# X12_Power_Distribuition.net
KiCad netlist of a schematic drawn in EAGLE
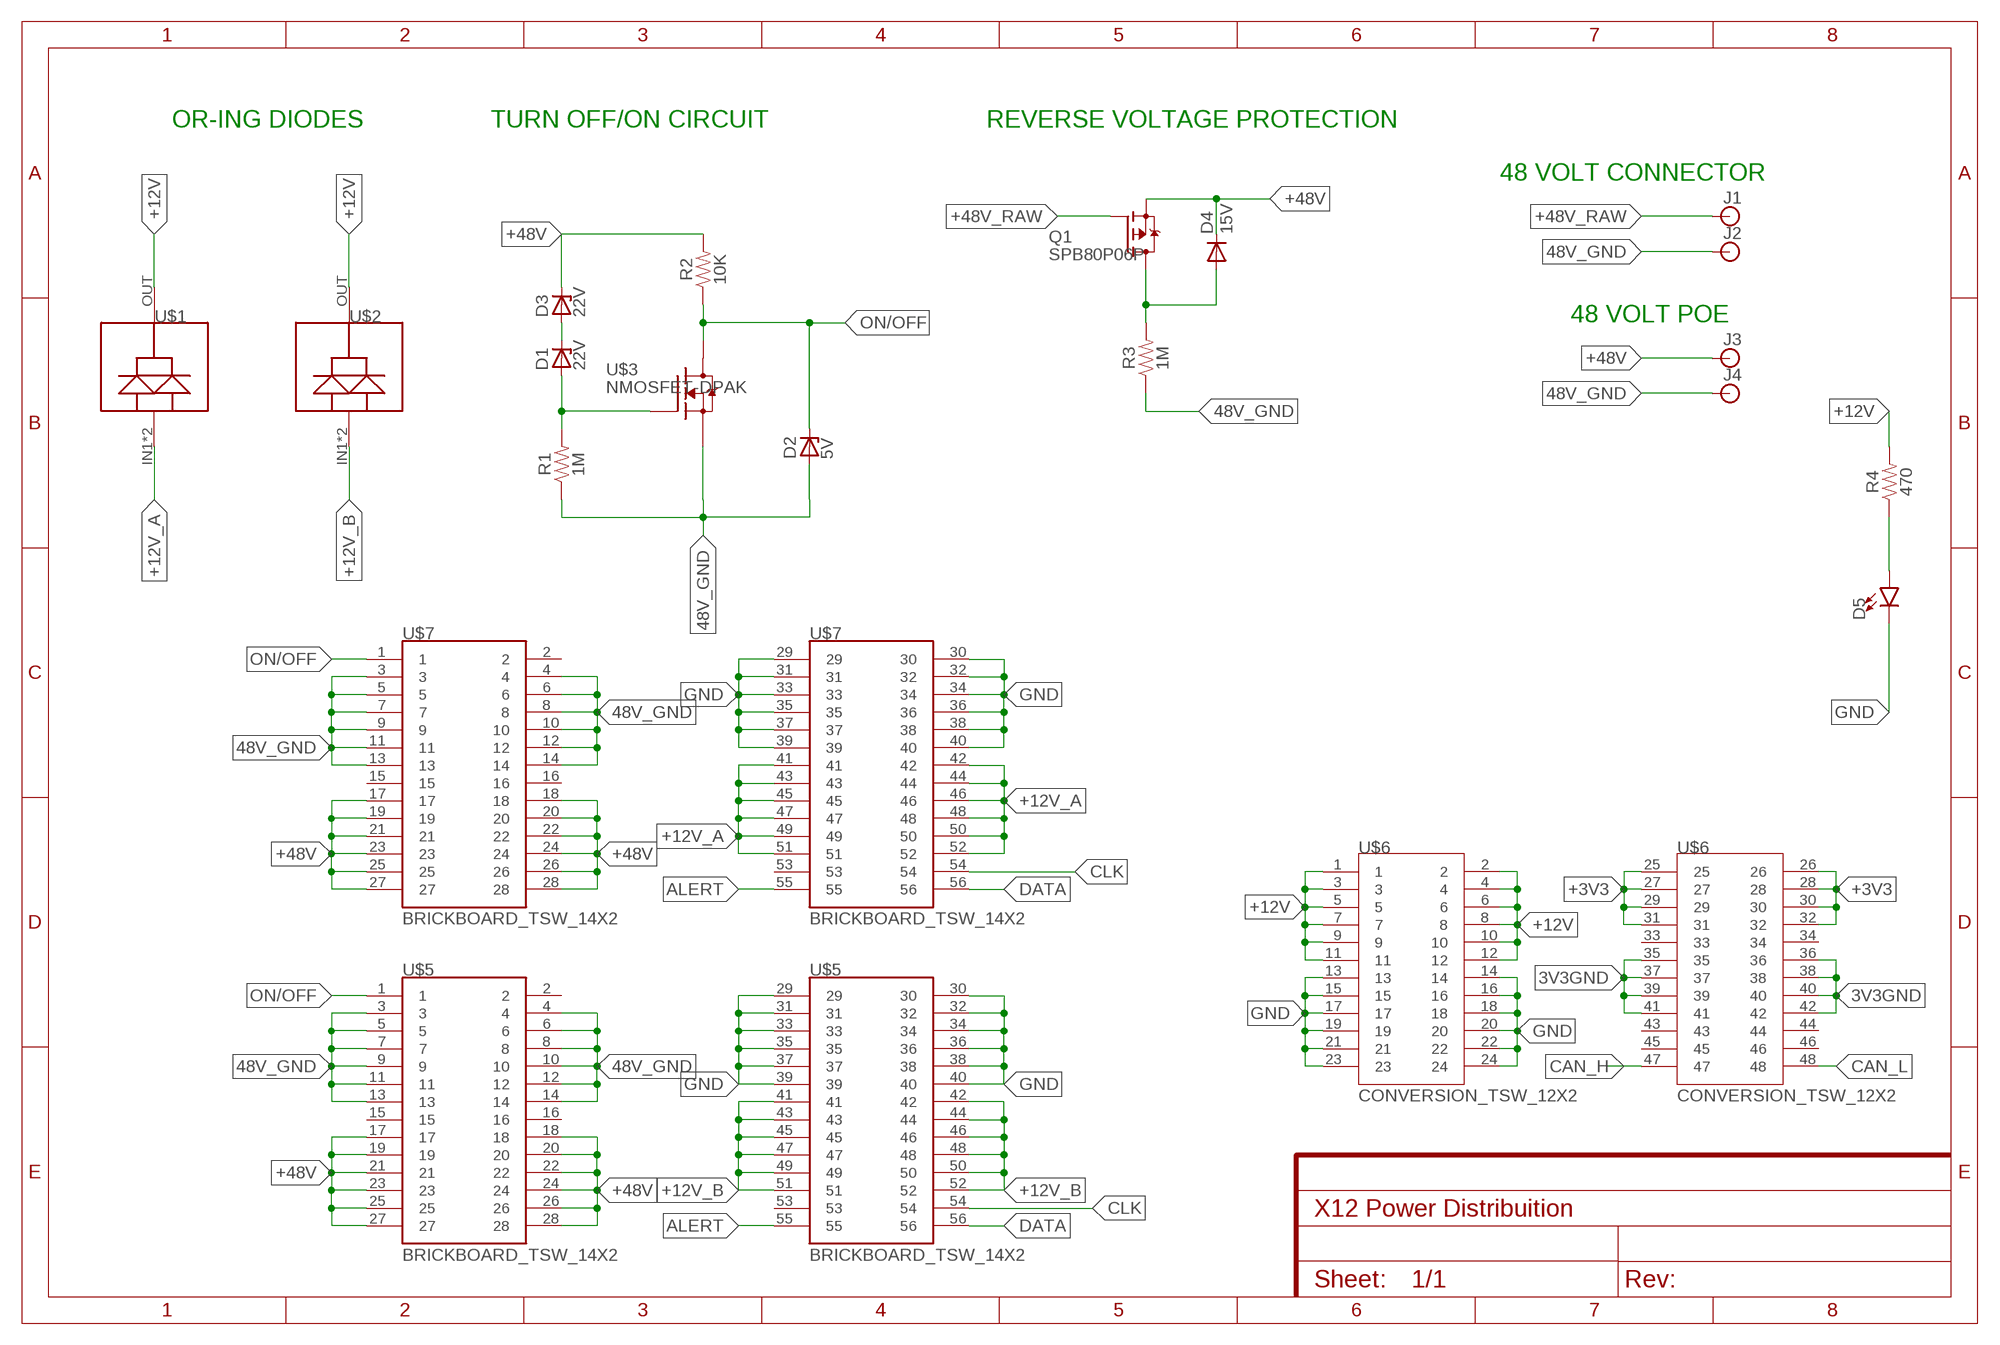
[diagram p0: schematic, sheet 1, part 1 of 2]
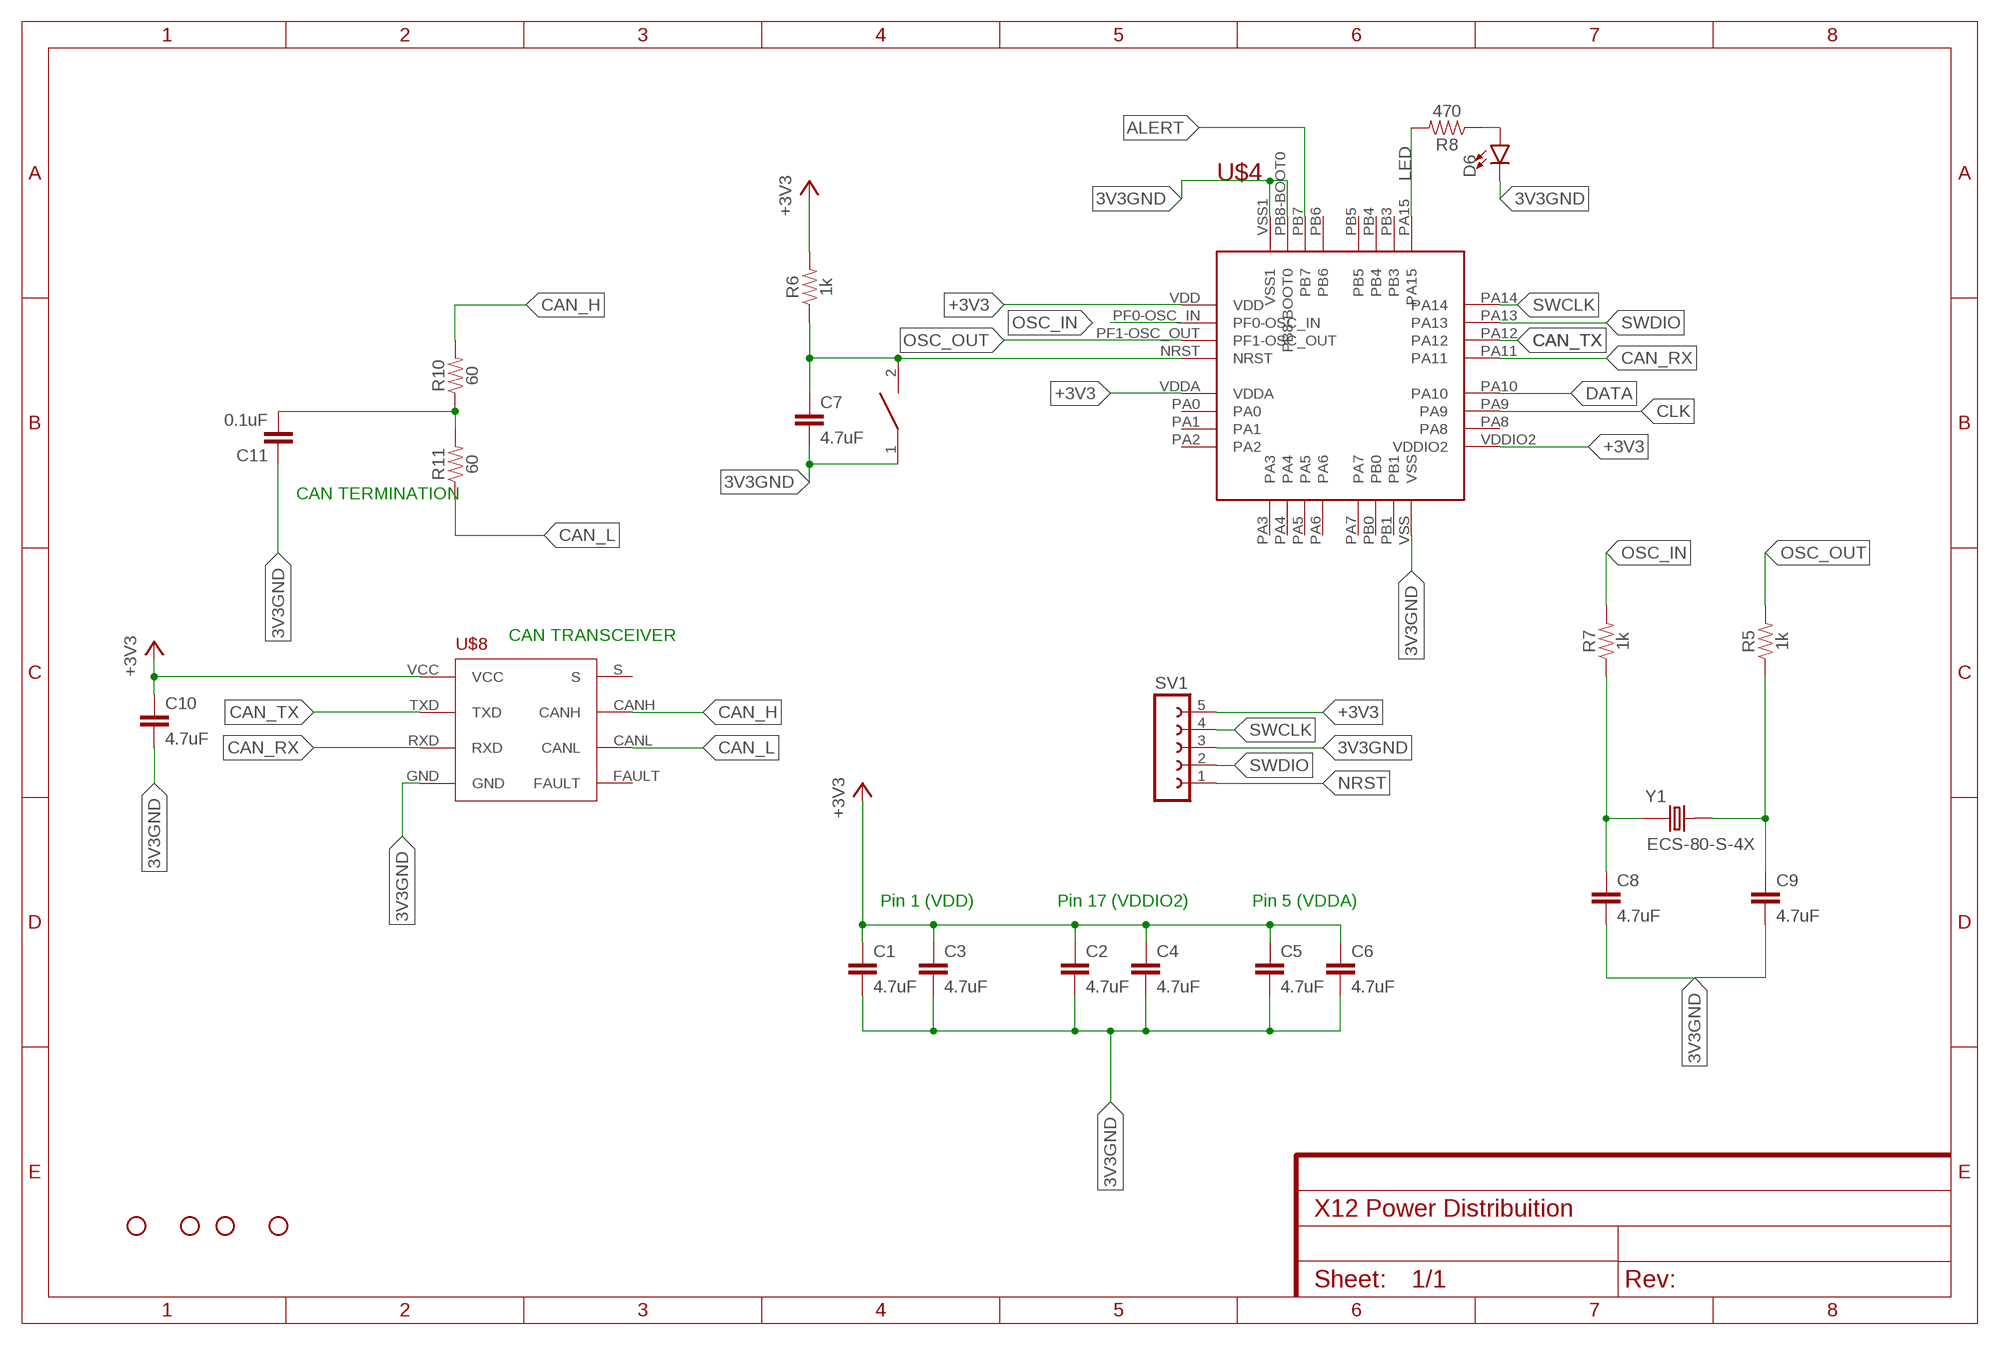
[diagram p1: schematic, sheet 1, part 2 of 2]

(export (version "E")
  (design (tool "Eeschema 10.0.6"))
  (components
    (comp (ref "C1")
      (value "4.7uF")
      (footprint "eagle-import:0603")
      (libsource (lib "eagle-import") (part "4.7UF0603"))
    )
    (comp (ref "C2")
      (value "4.7uF")
      (footprint "eagle-import:0603")
      (libsource (lib "eagle-import") (part "4.7UF0603"))
    )
    (comp (ref "C3")
      (value "4.7uF")
      (footprint "eagle-import:0603")
      (libsource (lib "eagle-import") (part "4.7UF0603"))
    )
    (comp (ref "C4")
      (value "4.7uF")
      (footprint "eagle-import:0603")
      (libsource (lib "eagle-import") (part "4.7UF0603"))
    )
    (comp (ref "C5")
      (value "4.7uF")
      (footprint "eagle-import:0603")
      (libsource (lib "eagle-import") (part "4.7UF0603"))
    )
    (comp (ref "C6")
      (value "4.7uF")
      (footprint "eagle-import:0603")
      (libsource (lib "eagle-import") (part "4.7UF0603"))
    )
    (comp (ref "C7")
      (value "4.7uF")
      (footprint "eagle-import:0603")
      (libsource (lib "eagle-import") (part "4.7UF0603"))
    )
    (comp (ref "C8")
      (value "4.7uF")
      (footprint "eagle-import:0603")
      (libsource (lib "eagle-import") (part "4.7UF0603"))
    )
    (comp (ref "C9")
      (value "4.7uF")
      (footprint "eagle-import:0603")
      (libsource (lib "eagle-import") (part "4.7UF0603"))
    )
    (comp (ref "C10")
      (value "4.7uF")
      (footprint "eagle-import:0603")
      (libsource (lib "eagle-import") (part "4.7UF0603"))
    )
    (comp (ref "C11")
      (value "0.1uF")
      (footprint "eagle-import:0603")
      (libsource (lib "eagle-import") (part "0.1UF-0603-25V-(+80/-20%)"))
    )
    (comp (ref "D1")
      (value "22V")
      (footprint "eagle-import:SOT23")
      (libsource (lib "eagle-import") (part "ZENER-DIODESOT23"))
    )
    (comp (ref "D2")
      (value "5V")
      (footprint "eagle-import:SOT23")
      (libsource (lib "eagle-import") (part "ZENER-DIODESOT23"))
    )
    (comp (ref "D3")
      (value "22V")
      (footprint "eagle-import:SOT23")
      (libsource (lib "eagle-import") (part "ZENER-DIODESOT23"))
    )
    (comp (ref "D4")
      (value "15V")
      (footprint "eagle-import:SOD123")
      (libsource (lib "eagle-import") (part "DIODE-SOD123"))
    )
    (comp (ref "D5")
      (value "LED0603")
      (footprint "eagle-import:LED-0603")
      (libsource (lib "eagle-import") (part "LED0603"))
    )
    (comp (ref "D6")
      (value "LED0603")
      (footprint "eagle-import:LED-0603")
      (libsource (lib "eagle-import") (part "LED0603"))
    )
    (comp (ref "H1")
      (value "STAND-OFF")
      (footprint "eagle-import:STAND-OFF")
      (libsource (lib "eagle-import") (part "STAND-OFF"))
    )
    (comp (ref "H2")
      (value "STAND-OFF")
      (footprint "eagle-import:STAND-OFF")
      (libsource (lib "eagle-import") (part "STAND-OFF"))
    )
    (comp (ref "H3")
      (value "STAND-OFF")
      (footprint "eagle-import:STAND-OFF")
      (libsource (lib "eagle-import") (part "STAND-OFF"))
    )
    (comp (ref "H4")
      (value "STAND-OFF")
      (footprint "eagle-import:STAND-OFF")
      (libsource (lib "eagle-import") (part "STAND-OFF"))
    )
    (comp (ref "J1")
      (value "BANANA_CONN")
      (footprint "eagle-import:BANANA_CONN")
      (libsource (lib "eagle-import") (part "BANANA_CONN"))
    )
    (comp (ref "J2")
      (value "BANANA_CONN")
      (footprint "eagle-import:BANANA_CONN")
      (libsource (lib "eagle-import") (part "BANANA_CONN"))
    )
    (comp (ref "J3")
      (value "BANANA_CONN")
      (footprint "eagle-import:BANANA_CONN")
      (libsource (lib "eagle-import") (part "BANANA_CONN"))
    )
    (comp (ref "J4")
      (value "BANANA_CONN")
      (footprint "eagle-import:BANANA_CONN")
      (libsource (lib "eagle-import") (part "BANANA_CONN"))
    )
    (comp (ref "Q1")
      (value "SPB80P06P")
      (footprint "eagle-import:TO263")
      (libsource (lib "eagle-import") (part "SPB80P06P"))
    )
    (comp (ref "R1")
      (value "1M")
      (footprint "eagle-import:0603")
      (fields (field (name "SPICEPREFIX") "R"))
      (libsource (lib "eagle-import") (part "RESISTOR0603"))
    )
    (comp (ref "R2")
      (value "10K")
      (footprint "eagle-import:0603")
      (fields (field (name "SPICEPREFIX") "R"))
      (libsource (lib "eagle-import") (part "RESISTOR0603"))
    )
    (comp (ref "R3")
      (value "1M")
      (footprint "eagle-import:0603")
      (fields (field (name "SPICEPREFIX") "R"))
      (libsource (lib "eagle-import") (part "RESISTOR0603"))
    )
    (comp (ref "R4")
      (value "470")
      (footprint "eagle-import:0603")
      (libsource (lib "eagle-import") (part "RESISTOR0603"))
    )
    (comp (ref "R5")
      (value "1k")
      (footprint "eagle-import:0603")
      (libsource (lib "eagle-import") (part "1KOHM-0603-1/10W-1%"))
    )
    (comp (ref "R6")
      (value "1k")
      (footprint "eagle-import:0603")
      (libsource (lib "eagle-import") (part "1KOHM-0603-1/10W-1%"))
    )
    (comp (ref "R7")
      (value "1k")
      (footprint "eagle-import:0603")
      (libsource (lib "eagle-import") (part "1KOHM-0603-1/10W-1%"))
    )
    (comp (ref "R8")
      (value "470")
      (footprint "eagle-import:0603")
      (libsource (lib "eagle-import") (part "RESISTOR0603"))
    )
    (comp (ref "R10")
      (value "60")
      (footprint "eagle-import:0603")
      (libsource (lib "eagle-import") (part "1KOHM-0603-1/10W-1%"))
    )
    (comp (ref "R11")
      (value "60")
      (footprint "eagle-import:0603")
      (libsource (lib "eagle-import") (part "1KOHM-0603-1/10W-1%"))
    )
    (comp (ref "RESET")
      (value "SWITCH")
      (footprint "eagle-import:SW_2512")
      (libsource (lib "eagle-import") (part "SWITCH"))
    )
    (comp (ref "SV1")
      (value "FE05-1")
      (footprint "eagle-import:FE05-1")
      (libsource (lib "eagle-import") (part "FE05-1"))
    )
    (comp (ref "U$1")
      (value "DIODE")
      (footprint "eagle-import:DIODE")
      (libsource (lib "eagle-import") (part "DIODE"))
    )
    (comp (ref "U$2")
      (value "DIODE")
      (footprint "eagle-import:DIODE")
      (libsource (lib "eagle-import") (part "DIODE"))
    )
    (comp (ref "U$3")
      (value "NMOSFET-DPAK")
      (footprint "eagle-import:DPAK")
      (libsource (lib "eagle-import") (part "NMOSFET-DPAK"))
    )
    (comp (ref "U$4")
      (value "STM32F042K6T6")
      (footprint "eagle-import:STM32F042K6T6")
      (libsource (lib "eagle-import") (part "STM32F042K6T6"))
    )
    (comp (ref "U$5")
      (value "BRICKBOARD_TSW_14X2")
      (footprint "eagle-import:BRICKBOARD_TSW_14X2")
      (libsource (lib "eagle-import") (part "BRICKBOARD_TSW_14X2"))
    )
    (comp (ref "U$6")
      (value "CONVERSION_TSW_12X2")
      (footprint "eagle-import:CONVERSION_TSW_12X2")
      (libsource (lib "eagle-import") (part "CONVERSION_TSW_12X2"))
    )
    (comp (ref "U$7")
      (value "BRICKBOARD_TSW_14X2")
      (footprint "eagle-import:BRICKBOARD_TSW_14X2")
      (libsource (lib "eagle-import") (part "BRICKBOARD_TSW_14X2"))
    )
    (comp (ref "U$8")
      (value "TCAN337D")
      (footprint "eagle-import:TCAN337D")
      (libsource (lib "eagle-import") (part "TCAN337D"))
    )
    (comp (ref "Y1")
      (value "ECS-80-S-4X")
      (footprint "eagle-import:XTAL_ECS-80-S-4X")
      (fields (field (name "DIGI-KEY_PART_NUMBER") "X1057-ND") (field (name "MF") "ECS International"))
      (libsource (lib "eagle-import") (part "ECS-80-S-4X"))
    )
  )
  (nets
    (net (code "1") (name "+3V3") (class "Default")
      (node (ref "C1") (pin "1") (pinfunction "1_1") (pintype "passive"))
      (node (ref "C10") (pin "1") (pinfunction "1_1") (pintype "passive"))
      (node (ref "C2") (pin "1") (pinfunction "1_1") (pintype "passive"))
      (node (ref "C3") (pin "1") (pinfunction "1_1") (pintype "passive"))
      (node (ref "C4") (pin "1") (pinfunction "1_1") (pintype "passive"))
      (node (ref "C5") (pin "1") (pinfunction "1_1") (pintype "passive"))
      (node (ref "C6") (pin "1") (pinfunction "1_1") (pintype "passive"))
      (node (ref "R6") (pin "2") (pinfunction "2_2") (pintype "passive"))
      (node (ref "SV1") (pin "5") (pinfunction "5_5") (pintype "passive"))
      (node (ref "U$4") (pin "VDD") (pinfunction "VDD_VDD") (pintype "bidirectional"))
      (node (ref "U$4") (pin "VDDA") (pinfunction "VDDA_VDDA") (pintype "bidirectional"))
      (node (ref "U$4") (pin "VDDIO2") (pinfunction "VDDIO2_VDDIO2") (pintype "bidirectional"))
      (node (ref "U$6") (pin "25") (pinfunction "25_25") (pintype "bidirectional"))
      (node (ref "U$6") (pin "26") (pinfunction "26_26") (pintype "bidirectional"))
      (node (ref "U$6") (pin "27") (pinfunction "27_27") (pintype "bidirectional"))
      (node (ref "U$6") (pin "28") (pinfunction "28_28") (pintype "bidirectional"))
      (node (ref "U$6") (pin "29") (pinfunction "29_29") (pintype "bidirectional"))
      (node (ref "U$6") (pin "30") (pinfunction "30_30") (pintype "bidirectional"))
      (node (ref "U$6") (pin "31") (pinfunction "31_31") (pintype "bidirectional"))
      (node (ref "U$6") (pin "32") (pinfunction "32_32") (pintype "bidirectional"))
      (node (ref "U$8") (pin "VCC") (pinfunction "VCC_VCC") (pintype "bidirectional"))
    )
    (net (code "2") (name "+12V") (class "Default")
      (node (ref "R4") (pin "2") (pinfunction "2_2") (pintype "passive"))
      (node (ref "U$1") (pin "OUT") (pinfunction "OUT_OUT") (pintype "bidirectional"))
      (node (ref "U$2") (pin "OUT") (pinfunction "OUT_OUT") (pintype "bidirectional"))
      (node (ref "U$6") (pin "1") (pinfunction "1_1") (pintype "bidirectional"))
      (node (ref "U$6") (pin "10") (pinfunction "10_10") (pintype "bidirectional"))
      (node (ref "U$6") (pin "11") (pinfunction "11_11") (pintype "bidirectional"))
      (node (ref "U$6") (pin "12") (pinfunction "12_12") (pintype "bidirectional"))
      (node (ref "U$6") (pin "2") (pinfunction "2_2") (pintype "bidirectional"))
      (node (ref "U$6") (pin "3") (pinfunction "3_3") (pintype "bidirectional"))
      (node (ref "U$6") (pin "4") (pinfunction "4_4") (pintype "bidirectional"))
      (node (ref "U$6") (pin "5") (pinfunction "5_5") (pintype "bidirectional"))
      (node (ref "U$6") (pin "6") (pinfunction "6_6") (pintype "bidirectional"))
      (node (ref "U$6") (pin "7") (pinfunction "7_7") (pintype "bidirectional"))
      (node (ref "U$6") (pin "8") (pinfunction "8_8") (pintype "bidirectional"))
      (node (ref "U$6") (pin "9") (pinfunction "9_9") (pintype "bidirectional"))
    )
    (net (code "3") (name "+12V_A") (class "Default")
      (node (ref "U$1") (pin "IN1") (pinfunction "IN2_IN1") (pintype "bidirectional"))
      (node (ref "U$1") (pin "IN2") (pinfunction "IN2_IN2") (pintype "bidirectional"))
      (node (ref "U$7") (pin "41") (pinfunction "41_41") (pintype "bidirectional"))
      (node (ref "U$7") (pin "42") (pinfunction "42_42") (pintype "bidirectional"))
      (node (ref "U$7") (pin "43") (pinfunction "43_43") (pintype "bidirectional"))
      (node (ref "U$7") (pin "44") (pinfunction "44_44") (pintype "bidirectional"))
      (node (ref "U$7") (pin "45") (pinfunction "45_45") (pintype "bidirectional"))
      (node (ref "U$7") (pin "46") (pinfunction "46_46") (pintype "bidirectional"))
      (node (ref "U$7") (pin "47") (pinfunction "47_47") (pintype "bidirectional"))
      (node (ref "U$7") (pin "48") (pinfunction "48_48") (pintype "bidirectional"))
      (node (ref "U$7") (pin "49") (pinfunction "49_49") (pintype "bidirectional"))
      (node (ref "U$7") (pin "50") (pinfunction "50_50") (pintype "bidirectional"))
      (node (ref "U$7") (pin "51") (pinfunction "51_51") (pintype "bidirectional"))
      (node (ref "U$7") (pin "52") (pinfunction "52_52") (pintype "bidirectional"))
    )
    (net (code "4") (name "+12V_B") (class "Default")
      (node (ref "U$2") (pin "IN1") (pinfunction "IN2_IN1") (pintype "bidirectional"))
      (node (ref "U$2") (pin "IN2") (pinfunction "IN2_IN2") (pintype "bidirectional"))
      (node (ref "U$5") (pin "41") (pinfunction "41_41") (pintype "bidirectional"))
      (node (ref "U$5") (pin "42") (pinfunction "42_42") (pintype "bidirectional"))
      (node (ref "U$5") (pin "43") (pinfunction "43_43") (pintype "bidirectional"))
      (node (ref "U$5") (pin "44") (pinfunction "44_44") (pintype "bidirectional"))
      (node (ref "U$5") (pin "45") (pinfunction "45_45") (pintype "bidirectional"))
      (node (ref "U$5") (pin "46") (pinfunction "46_46") (pintype "bidirectional"))
      (node (ref "U$5") (pin "47") (pinfunction "47_47") (pintype "bidirectional"))
      (node (ref "U$5") (pin "48") (pinfunction "48_48") (pintype "bidirectional"))
      (node (ref "U$5") (pin "49") (pinfunction "49_49") (pintype "bidirectional"))
      (node (ref "U$5") (pin "50") (pinfunction "50_50") (pintype "bidirectional"))
      (node (ref "U$5") (pin "51") (pinfunction "51_51") (pintype "bidirectional"))
      (node (ref "U$5") (pin "52") (pinfunction "52_52") (pintype "bidirectional"))
    )
    (net (code "5") (name "+48V") (class "Default")
      (node (ref "D3") (pin "3") (pinfunction "C_3") (pintype "passive"))
      (node (ref "D4") (pin "C") (pinfunction "C_C") (pintype "passive"))
      (node (ref "J3") (pin "P$1") (pinfunction "1_P$1") (pintype "passive"))
      (node (ref "Q1") (pin "2") (pinfunction "S_2") (pintype "passive"))
      (node (ref "R2") (pin "2") (pinfunction "2_2") (pintype "passive"))
      (node (ref "U$5") (pin "17") (pinfunction "17_17") (pintype "bidirectional"))
      (node (ref "U$5") (pin "18") (pinfunction "18_18") (pintype "bidirectional"))
      (node (ref "U$5") (pin "19") (pinfunction "19_19") (pintype "bidirectional"))
      (node (ref "U$5") (pin "20") (pinfunction "20_20") (pintype "bidirectional"))
      (node (ref "U$5") (pin "21") (pinfunction "21_21") (pintype "bidirectional"))
      (node (ref "U$5") (pin "22") (pinfunction "22_22") (pintype "bidirectional"))
      (node (ref "U$5") (pin "23") (pinfunction "23_23") (pintype "bidirectional"))
      (node (ref "U$5") (pin "24") (pinfunction "24_24") (pintype "bidirectional"))
      (node (ref "U$5") (pin "25") (pinfunction "25_25") (pintype "bidirectional"))
      (node (ref "U$5") (pin "26") (pinfunction "26_26") (pintype "bidirectional"))
      (node (ref "U$5") (pin "27") (pinfunction "27_27") (pintype "bidirectional"))
      (node (ref "U$5") (pin "28") (pinfunction "28_28") (pintype "bidirectional"))
      (node (ref "U$7") (pin "17") (pinfunction "17_17") (pintype "bidirectional"))
      (node (ref "U$7") (pin "18") (pinfunction "18_18") (pintype "bidirectional"))
      (node (ref "U$7") (pin "19") (pinfunction "19_19") (pintype "bidirectional"))
      (node (ref "U$7") (pin "20") (pinfunction "20_20") (pintype "bidirectional"))
      (node (ref "U$7") (pin "21") (pinfunction "21_21") (pintype "bidirectional"))
      (node (ref "U$7") (pin "22") (pinfunction "22_22") (pintype "bidirectional"))
      (node (ref "U$7") (pin "23") (pinfunction "23_23") (pintype "bidirectional"))
      (node (ref "U$7") (pin "24") (pinfunction "24_24") (pintype "bidirectional"))
      (node (ref "U$7") (pin "25") (pinfunction "25_25") (pintype "bidirectional"))
      (node (ref "U$7") (pin "26") (pinfunction "26_26") (pintype "bidirectional"))
      (node (ref "U$7") (pin "27") (pinfunction "27_27") (pintype "bidirectional"))
      (node (ref "U$7") (pin "28") (pinfunction "28_28") (pintype "bidirectional"))
    )
    (net (code "6") (name "+48V_RAW") (class "Default")
      (node (ref "J1") (pin "P$1") (pinfunction "1_P$1") (pintype "passive"))
      (node (ref "Q1") (pin "1") (pinfunction "G_1") (pintype "passive"))
    )
    (net (code "7") (name "/LED") (class "Default")
      (node (ref "R8") (pin "2") (pinfunction "2_2") (pintype "passive"))
      (node (ref "U$4") (pin "PA15") (pinfunction "PA15_PA15") (pintype "bidirectional"))
    )
    (net (code "8") (name "3V3GND") (class "Default")
      (node (ref "C1") (pin "2") (pinfunction "2_2") (pintype "passive"))
      (node (ref "C10") (pin "2") (pinfunction "2_2") (pintype "passive"))
      (node (ref "C11") (pin "1") (pinfunction "1_1") (pintype "passive"))
      (node (ref "C2") (pin "2") (pinfunction "2_2") (pintype "passive"))
      (node (ref "C3") (pin "2") (pinfunction "2_2") (pintype "passive"))
      (node (ref "C4") (pin "2") (pinfunction "2_2") (pintype "passive"))
      (node (ref "C5") (pin "2") (pinfunction "2_2") (pintype "passive"))
      (node (ref "C6") (pin "2") (pinfunction "2_2") (pintype "passive"))
      (node (ref "C7") (pin "2") (pinfunction "2_2") (pintype "passive"))
      (node (ref "C8") (pin "2") (pinfunction "2_2") (pintype "passive"))
      (node (ref "C9") (pin "2") (pinfunction "2_2") (pintype "passive"))
      (node (ref "D6") (pin "C") (pinfunction "C_C") (pintype "passive"))
      (node (ref "RESET") (pin "1") (pinfunction "P$1_1") (pintype "bidirectional"))
      (node (ref "SV1") (pin "3") (pinfunction "3_3") (pintype "passive"))
      (node (ref "U$4") (pin "PB8-BOOT0") (pinfunction "PB8-BOOT0_PB8-BOOT0") (pintype "bidirectional"))
      (node (ref "U$4") (pin "VSS") (pinfunction "VSS_VSS") (pintype "bidirectional"))
      (node (ref "U$4") (pin "VSS1") (pinfunction "VSS1_VSS1") (pintype "bidirectional"))
      (node (ref "U$6") (pin "35") (pinfunction "35_35") (pintype "bidirectional"))
      (node (ref "U$6") (pin "36") (pinfunction "36_36") (pintype "bidirectional"))
      (node (ref "U$6") (pin "37") (pinfunction "37_37") (pintype "bidirectional"))
      (node (ref "U$6") (pin "38") (pinfunction "38_38") (pintype "bidirectional"))
      (node (ref "U$6") (pin "39") (pinfunction "39_39") (pintype "bidirectional"))
      (node (ref "U$6") (pin "40") (pinfunction "40_40") (pintype "bidirectional"))
      (node (ref "U$6") (pin "41") (pinfunction "41_41") (pintype "bidirectional"))
      (node (ref "U$6") (pin "42") (pinfunction "42_42") (pintype "bidirectional"))
      (node (ref "U$8") (pin "GND") (pinfunction "GND_GND") (pintype "bidirectional"))
    )
    (net (code "9") (name "48V_GND") (class "Default")
      (node (ref "D2") (pin "1") (pinfunction "A_1") (pintype "passive"))
      (node (ref "J2") (pin "P$1") (pinfunction "1_P$1") (pintype "passive"))
      (node (ref "J4") (pin "P$1") (pinfunction "1_P$1") (pintype "passive"))
      (node (ref "R1") (pin "1") (pinfunction "1_1") (pintype "passive"))
      (node (ref "R3") (pin "1") (pinfunction "1_1") (pintype "passive"))
      (node (ref "U$3") (pin "3") (pinfunction "S_3") (pintype "passive"))
      (node (ref "U$5") (pin "10") (pinfunction "10_10") (pintype "bidirectional"))
      (node (ref "U$5") (pin "11") (pinfunction "11_11") (pintype "bidirectional"))
      (node (ref "U$5") (pin "12") (pinfunction "12_12") (pintype "bidirectional"))
      (node (ref "U$5") (pin "13") (pinfunction "13_13") (pintype "bidirectional"))
      (node (ref "U$5") (pin "14") (pinfunction "14_14") (pintype "bidirectional"))
      (node (ref "U$5") (pin "3") (pinfunction "3_3") (pintype "bidirectional"))
      (node (ref "U$5") (pin "4") (pinfunction "4_4") (pintype "bidirectional"))
      (node (ref "U$5") (pin "5") (pinfunction "5_5") (pintype "bidirectional"))
      (node (ref "U$5") (pin "6") (pinfunction "6_6") (pintype "bidirectional"))
      (node (ref "U$5") (pin "7") (pinfunction "7_7") (pintype "bidirectional"))
      (node (ref "U$5") (pin "8") (pinfunction "8_8") (pintype "bidirectional"))
      (node (ref "U$5") (pin "9") (pinfunction "9_9") (pintype "bidirectional"))
      (node (ref "U$7") (pin "10") (pinfunction "10_10") (pintype "bidirectional"))
      (node (ref "U$7") (pin "11") (pinfunction "11_11") (pintype "bidirectional"))
      (node (ref "U$7") (pin "12") (pinfunction "12_12") (pintype "bidirectional"))
      (node (ref "U$7") (pin "13") (pinfunction "13_13") (pintype "bidirectional"))
      (node (ref "U$7") (pin "14") (pinfunction "14_14") (pintype "bidirectional"))
      (node (ref "U$7") (pin "3") (pinfunction "3_3") (pintype "bidirectional"))
      (node (ref "U$7") (pin "4") (pinfunction "4_4") (pintype "bidirectional"))
      (node (ref "U$7") (pin "5") (pinfunction "5_5") (pintype "bidirectional"))
      (node (ref "U$7") (pin "6") (pinfunction "6_6") (pintype "bidirectional"))
      (node (ref "U$7") (pin "7") (pinfunction "7_7") (pintype "bidirectional"))
      (node (ref "U$7") (pin "8") (pinfunction "8_8") (pintype "bidirectional"))
      (node (ref "U$7") (pin "9") (pinfunction "9_9") (pintype "bidirectional"))
    )
    (net (code "10") (name "ALERT") (class "Default")
      (node (ref "U$4") (pin "PB7") (pinfunction "PB7_PB7") (pintype "bidirectional"))
      (node (ref "U$5") (pin "55") (pinfunction "55_55") (pintype "bidirectional"))
      (node (ref "U$7") (pin "55") (pinfunction "55_55") (pintype "bidirectional"))
    )
    (net (code "11") (name "CAN_H") (class "Default")
      (node (ref "R10") (pin "2") (pinfunction "2_2") (pintype "passive"))
      (node (ref "U$6") (pin "47") (pinfunction "47_47") (pintype "bidirectional"))
      (node (ref "U$8") (pin "CANH") (pinfunction "CANH_CANH") (pintype "bidirectional"))
    )
    (net (code "12") (name "CAN_L") (class "Default")
      (node (ref "R11") (pin "1") (pinfunction "1_1") (pintype "passive"))
      (node (ref "U$6") (pin "48") (pinfunction "48_48") (pintype "bidirectional"))
      (node (ref "U$8") (pin "CANL") (pinfunction "CANL_CANL") (pintype "bidirectional"))
    )
    (net (code "13") (name "CAN_RX") (class "Default")
      (node (ref "U$4") (pin "PA11") (pinfunction "PA11_PA11") (pintype "bidirectional"))
      (node (ref "U$8") (pin "RXD") (pinfunction "RXD_RXD") (pintype "bidirectional"))
    )
    (net (code "14") (name "CAN_TX") (class "Default")
      (node (ref "U$4") (pin "PA12") (pinfunction "PA12_PA12") (pintype "bidirectional"))
      (node (ref "U$8") (pin "TXD") (pinfunction "TXD_TXD") (pintype "bidirectional"))
    )
    (net (code "15") (name "CLK") (class "Default")
      (node (ref "U$4") (pin "PA9") (pinfunction "PA9_PA9") (pintype "bidirectional"))
      (node (ref "U$5") (pin "54") (pinfunction "54_54") (pintype "bidirectional"))
      (node (ref "U$7") (pin "54") (pinfunction "54_54") (pintype "bidirectional"))
    )
    (net (code "16") (name "DATA") (class "Default")
      (node (ref "U$4") (pin "PA10") (pinfunction "PA10_PA10") (pintype "bidirectional"))
      (node (ref "U$5") (pin "56") (pinfunction "56_56") (pintype "bidirectional"))
      (node (ref "U$7") (pin "56") (pinfunction "56_56") (pintype "bidirectional"))
    )
    (net (code "17") (name "GND") (class "Default")
      (node (ref "D5") (pin "C") (pinfunction "C_C") (pintype "passive"))
      (node (ref "U$5") (pin "29") (pinfunction "29_29") (pintype "bidirectional"))
      (node (ref "U$5") (pin "30") (pinfunction "30_30") (pintype "bidirectional"))
      (node (ref "U$5") (pin "31") (pinfunction "31_31") (pintype "bidirectional"))
      (node (ref "U$5") (pin "32") (pinfunction "32_32") (pintype "bidirectional"))
      (node (ref "U$5") (pin "33") (pinfunction "33_33") (pintype "bidirectional"))
      (node (ref "U$5") (pin "34") (pinfunction "34_34") (pintype "bidirectional"))
      (node (ref "U$5") (pin "35") (pinfunction "35_35") (pintype "bidirectional"))
      (node (ref "U$5") (pin "36") (pinfunction "36_36") (pintype "bidirectional"))
      (node (ref "U$5") (pin "37") (pinfunction "37_37") (pintype "bidirectional"))
      (node (ref "U$5") (pin "38") (pinfunction "38_38") (pintype "bidirectional"))
      (node (ref "U$5") (pin "39") (pinfunction "39_39") (pintype "bidirectional"))
      (node (ref "U$5") (pin "40") (pinfunction "40_40") (pintype "bidirectional"))
      (node (ref "U$6") (pin "13") (pinfunction "13_13") (pintype "bidirectional"))
      (node (ref "U$6") (pin "14") (pinfunction "14_14") (pintype "bidirectional"))
      (node (ref "U$6") (pin "15") (pinfunction "15_15") (pintype "bidirectional"))
      (node (ref "U$6") (pin "16") (pinfunction "16_16") (pintype "bidirectional"))
      (node (ref "U$6") (pin "17") (pinfunction "17_17") (pintype "bidirectional"))
      (node (ref "U$6") (pin "18") (pinfunction "18_18") (pintype "bidirectional"))
      (node (ref "U$6") (pin "19") (pinfunction "19_19") (pintype "bidirectional"))
      (node (ref "U$6") (pin "20") (pinfunction "20_20") (pintype "bidirectional"))
      (node (ref "U$6") (pin "21") (pinfunction "21_21") (pintype "bidirectional"))
      (node (ref "U$6") (pin "22") (pinfunction "22_22") (pintype "bidirectional"))
      (node (ref "U$6") (pin "23") (pinfunction "23_23") (pintype "bidirectional"))
      (node (ref "U$6") (pin "24") (pinfunction "24_24") (pintype "bidirectional"))
      (node (ref "U$7") (pin "29") (pinfunction "29_29") (pintype "bidirectional"))
      (node (ref "U$7") (pin "30") (pinfunction "30_30") (pintype "bidirectional"))
      (node (ref "U$7") (pin "31") (pinfunction "31_31") (pintype "bidirectional"))
      (node (ref "U$7") (pin "32") (pinfunction "32_32") (pintype "bidirectional"))
      (node (ref "U$7") (pin "33") (pinfunction "33_33") (pintype "bidirectional"))
      (node (ref "U$7") (pin "34") (pinfunction "34_34") (pintype "bidirectional"))
      (node (ref "U$7") (pin "35") (pinfunction "35_35") (pintype "bidirectional"))
      (node (ref "U$7") (pin "36") (pinfunction "36_36") (pintype "bidirectional"))
      (node (ref "U$7") (pin "37") (pinfunction "37_37") (pintype "bidirectional"))
      (node (ref "U$7") (pin "38") (pinfunction "38_38") (pintype "bidirectional"))
      (node (ref "U$7") (pin "39") (pinfunction "39_39") (pintype "bidirectional"))
      (node (ref "U$7") (pin "40") (pinfunction "40_40") (pintype "bidirectional"))
    )
    (net (code "18") (name "NRST") (class "Default")
      (node (ref "C7") (pin "1") (pinfunction "1_1") (pintype "passive"))
      (node (ref "R6") (pin "1") (pinfunction "1_1") (pintype "passive"))
      (node (ref "RESET") (pin "2") (pinfunction "P$2_2") (pintype "bidirectional"))
      (node (ref "SV1") (pin "1") (pinfunction "1_1") (pintype "passive"))
      (node (ref "U$4") (pin "NRST") (pinfunction "NRST_NRST") (pintype "bidirectional"))
    )
    (net (code "19") (name "Net-(C8-Pad1)") (class "Default")
      (node (ref "C8") (pin "1") (pinfunction "1_1") (pintype "passive"))
      (node (ref "R7") (pin "1") (pinfunction "1_1") (pintype "passive"))
      (node (ref "Y1") (pin "1") (pinfunction "1_1") (pintype "passive"))
    )
    (net (code "20") (name "Net-(C9-Pad1)") (class "Default")
      (node (ref "C9") (pin "1") (pinfunction "1_1") (pintype "passive"))
      (node (ref "R5") (pin "1") (pinfunction "1_1") (pintype "passive"))
      (node (ref "Y1") (pin "2") (pinfunction "2_2") (pintype "passive"))
    )
    (net (code "21") (name "Net-(C11-Pad2)") (class "Default")
      (node (ref "C11") (pin "2") (pinfunction "2_2") (pintype "passive"))
      (node (ref "R10") (pin "1") (pinfunction "1_1") (pintype "passive"))
      (node (ref "R11") (pin "2") (pinfunction "2_2") (pintype "passive"))
    )
    (net (code "22") (name "Net-(D1-A)") (class "Default")
      (node (ref "D1") (pin "1") (pinfunction "A_1") (pintype "passive"))
      (node (ref "R1") (pin "2") (pinfunction "2_2") (pintype "passive"))
      (node (ref "U$3") (pin "1") (pinfunction "G_1") (pintype "passive"))
    )
    (net (code "23") (name "Net-(D1-C)") (class "Default")
      (node (ref "D1") (pin "3") (pinfunction "C_3") (pintype "passive"))
      (node (ref "D3") (pin "1") (pinfunction "A_1") (pintype "passive"))
    )
    (net (code "24") (name "Net-(D5-PadA)") (class "Default")
      (node (ref "D5") (pin "A") (pinfunction "A_A") (pintype "passive"))
      (node (ref "R4") (pin "1") (pinfunction "1_1") (pintype "passive"))
    )
    (net (code "25") (name "Net-(D6-PadA)") (class "Default")
      (node (ref "D6") (pin "A") (pinfunction "A_A") (pintype "passive"))
      (node (ref "R8") (pin "1") (pinfunction "1_1") (pintype "passive"))
    )
    (net (code "26") (name "Net-(Q1-D)") (class "Default")
      (node (ref "D4") (pin "A") (pinfunction "A_A") (pintype "passive"))
      (node (ref "Q1") (pin "3") (pinfunction "D_3") (pintype "passive"))
      (node (ref "R3") (pin "2") (pinfunction "2_2") (pintype "passive"))
    )
    (net (code "27") (name "ON{slash}OFF") (class "Default")
      (node (ref "D2") (pin "3") (pinfunction "C_3") (pintype "passive"))
      (node (ref "R2") (pin "1") (pinfunction "1_1") (pintype "passive"))
      (node (ref "U$3") (pin "4") (pinfunction "D1_4") (pintype "passive"))
      (node (ref "U$5") (pin "1") (pinfunction "1_1") (pintype "bidirectional"))
      (node (ref "U$7") (pin "1") (pinfunction "1_1") (pintype "bidirectional"))
    )
    (net (code "28") (name "OSC_IN") (class "Default")
      (node (ref "R7") (pin "2") (pinfunction "2_2") (pintype "passive"))
      (node (ref "U$4") (pin "PF0-OSC_IN") (pinfunction "PF0-OSC_IN_PF0-OSC_IN") (pintype "bidirectional"))
    )
    (net (code "29") (name "OSC_OUT") (class "Default")
      (node (ref "R5") (pin "2") (pinfunction "2_2") (pintype "passive"))
      (node (ref "U$4") (pin "PF1-OSC_OUT") (pinfunction "PF1-OSC_OUT_PF1-OSC_OUT") (pintype "bidirectional"))
    )
    (net (code "30") (name "SWCLK") (class "Default")
      (node (ref "SV1") (pin "4") (pinfunction "4_4") (pintype "passive"))
      (node (ref "U$4") (pin "PA14") (pinfunction "PA14_PA14") (pintype "bidirectional"))
    )
    (net (code "31") (name "SWDIO") (class "Default")
      (node (ref "SV1") (pin "2") (pinfunction "2_2") (pintype "passive"))
      (node (ref "U$4") (pin "PA13") (pinfunction "PA13_PA13") (pintype "bidirectional"))
    )
    (net (code "32") (name "unconnected-(U$4-PadPA0)") (class "Default")
      (node (ref "U$4") (pin "PA0") (pinfunction "PA0_PA0") (pintype "bidirectional"))
    )
    (net (code "33") (name "unconnected-(U$4-PadPA1)") (class "Default")
      (node (ref "U$4") (pin "PA1") (pinfunction "PA1_PA1") (pintype "bidirectional"))
    )
    (net (code "34") (name "unconnected-(U$4-PadPA2)") (class "Default")
      (node (ref "U$4") (pin "PA2") (pinfunction "PA2_PA2") (pintype "bidirectional"))
    )
    (net (code "35") (name "unconnected-(U$4-PadPA3)") (class "Default")
      (node (ref "U$4") (pin "PA3") (pinfunction "PA3_PA3") (pintype "bidirectional"))
    )
    (net (code "36") (name "unconnected-(U$4-PadPA4)") (class "Default")
      (node (ref "U$4") (pin "PA4") (pinfunction "PA4_PA4") (pintype "bidirectional"))
    )
    (net (code "37") (name "unconnected-(U$4-PadPA5)") (class "Default")
      (node (ref "U$4") (pin "PA5") (pinfunction "PA5_PA5") (pintype "bidirectional"))
    )
    (net (code "38") (name "unconnected-(U$4-PadPA6)") (class "Default")
      (node (ref "U$4") (pin "PA6") (pinfunction "PA6_PA6") (pintype "bidirectional"))
    )
    (net (code "39") (name "unconnected-(U$4-PadPA7)") (class "Default")
      (node (ref "U$4") (pin "PA7") (pinfunction "PA7_PA7") (pintype "bidirectional"))
    )
    (net (code "40") (name "unconnected-(U$4-PadPA8)") (class "Default")
      (node (ref "U$4") (pin "PA8") (pinfunction "PA8_PA8") (pintype "bidirectional"))
    )
    (net (code "41") (name "unconnected-(U$4-PadPB0)") (class "Default")
      (node (ref "U$4") (pin "PB0") (pinfunction "PB0_PB0") (pintype "bidirectional"))
    )
    (net (code "42") (name "unconnected-(U$4-PadPB1)") (class "Default")
      (node (ref "U$4") (pin "PB1") (pinfunction "PB1_PB1") (pintype "bidirectional"))
    )
    (net (code "43") (name "unconnected-(U$4-PadPB3)") (class "Default")
      (node (ref "U$4") (pin "PB3") (pinfunction "PB3_PB3") (pintype "bidirectional"))
    )
    (net (code "44") (name "unconnected-(U$4-PadPB4)") (class "Default")
      (node (ref "U$4") (pin "PB4") (pinfunction "PB4_PB4") (pintype "bidirectional"))
    )
    (net (code "45") (name "unconnected-(U$4-PadPB5)") (class "Default")
      (node (ref "U$4") (pin "PB5") (pinfunction "PB5_PB5") (pintype "bidirectional"))
    )
    (net (code "46") (name "unconnected-(U$4-PadPB6)") (class "Default")
      (node (ref "U$4") (pin "PB6") (pinfunction "PB6_PB6") (pintype "bidirectional"))
    )
    (net (code "47") (name "unconnected-(U$5-Pad2)") (class "Default")
      (node (ref "U$5") (pin "2") (pinfunction "2_2") (pintype "bidirectional"))
    )
    (net (code "48") (name "unconnected-(U$5-Pad15)") (class "Default")
      (node (ref "U$5") (pin "15") (pinfunction "15_15") (pintype "bidirectional"))
    )
    (net (code "49") (name "unconnected-(U$5-Pad16)") (class "Default")
      (node (ref "U$5") (pin "16") (pinfunction "16_16") (pintype "bidirectional"))
    )
    (net (code "50") (name "unconnected-(U$5-Pad53)") (class "Default")
      (node (ref "U$5") (pin "53") (pinfunction "53_53") (pintype "bidirectional"))
    )
    (net (code "51") (name "unconnected-(U$6-Pad33)") (class "Default")
      (node (ref "U$6") (pin "33") (pinfunction "33_33") (pintype "bidirectional"))
    )
    (net (code "52") (name "unconnected-(U$6-Pad34)") (class "Default")
      (node (ref "U$6") (pin "34") (pinfunction "34_34") (pintype "bidirectional"))
    )
    (net (code "53") (name "unconnected-(U$6-Pad43)") (class "Default")
      (node (ref "U$6") (pin "43") (pinfunction "43_43") (pintype "bidirectional"))
    )
    (net (code "54") (name "unconnected-(U$6-Pad44)") (class "Default")
      (node (ref "U$6") (pin "44") (pinfunction "44_44") (pintype "bidirectional"))
    )
    (net (code "55") (name "unconnected-(U$6-Pad45)") (class "Default")
      (node (ref "U$6") (pin "45") (pinfunction "45_45") (pintype "bidirectional"))
    )
    (net (code "56") (name "unconnected-(U$6-Pad46)") (class "Default")
      (node (ref "U$6") (pin "46") (pinfunction "46_46") (pintype "bidirectional"))
    )
    (net (code "57") (name "unconnected-(U$7-Pad2)") (class "Default")
      (node (ref "U$7") (pin "2") (pinfunction "2_2") (pintype "bidirectional"))
    )
    (net (code "58") (name "unconnected-(U$7-Pad15)") (class "Default")
      (node (ref "U$7") (pin "15") (pinfunction "15_15") (pintype "bidirectional"))
    )
    (net (code "59") (name "unconnected-(U$7-Pad16)") (class "Default")
      (node (ref "U$7") (pin "16") (pinfunction "16_16") (pintype "bidirectional"))
    )
    (net (code "60") (name "unconnected-(U$7-Pad53)") (class "Default")
      (node (ref "U$7") (pin "53") (pinfunction "53_53") (pintype "bidirectional"))
    )
    (net (code "61") (name "unconnected-(U$8-PadFAULT)") (class "Default")
      (node (ref "U$8") (pin "FAULT") (pinfunction "FAULT_FAULT") (pintype "bidirectional"))
    )
    (net (code "62") (name "unconnected-(U$8-PadS)") (class "Default")
      (node (ref "U$8") (pin "S") (pinfunction "S_S") (pintype "bidirectional"))
    )
  )
)
